# schematic.net
KiCad netlist of a schematic drawn in EasyEDA
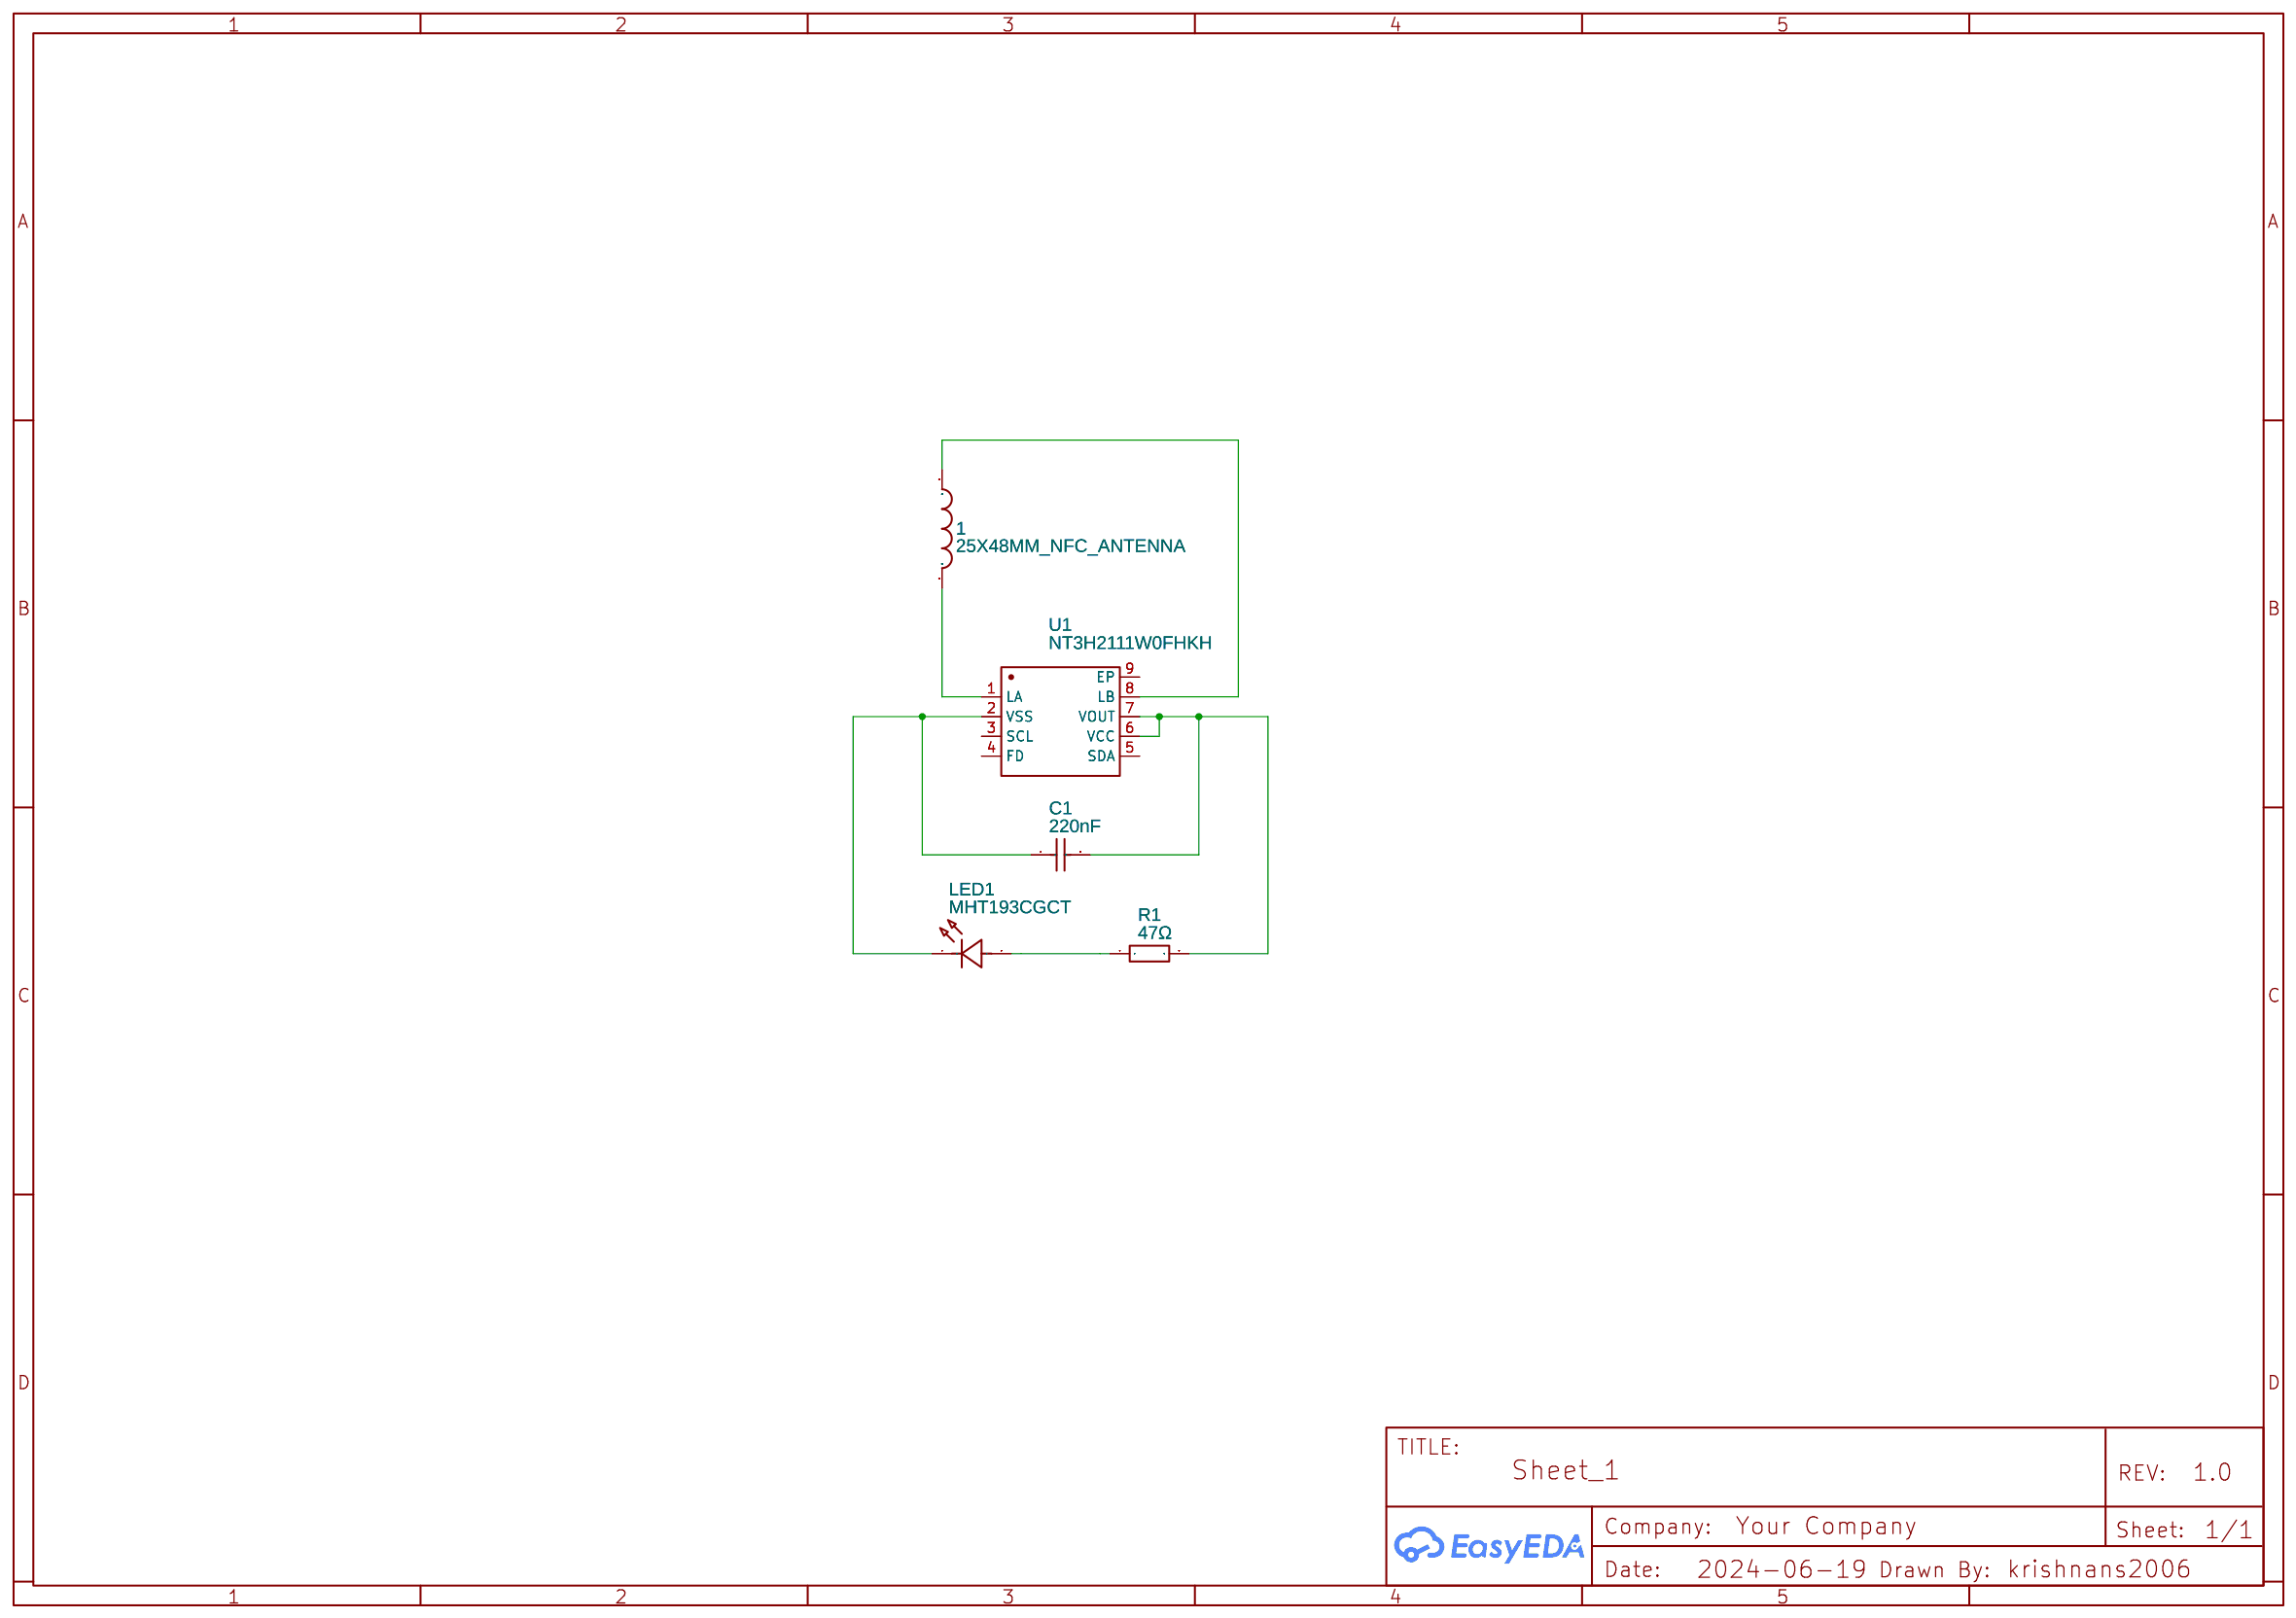
[diagram p0: schematic sheet]

(export (version "E")
  (design (tool "Eeschema 10.0.6"))
  (components
    (comp (ref "1") (value "25X48MM_NFC_ANTENNA") (libsource (lib "") (part "25X48MM_NFC_ANTENNA")))
    (comp (ref "C1")
      (value "220nF")
      (fields
        (field (name "Manufacturer Part") "CL10B224KA8NNNC")
        (field (name "Manufacturer") "SAMSUNG(三星)")
      )
      (libsource (lib "") (part "CL10B224KA8NNNC"))
    )
    (comp (ref "LED1")
      (value "MHT193CGCT")
      (fields (field (name "Manufacturer") "MEIHUA(美华)"))
      (libsource (lib "") (part "MHT193CGCT"))
    )
    (comp (ref "R1")
      (value "47Ω")
      (fields
        (field (name "Manufacturer Part") "0603WAF470JT5E")
        (field (name "Manufacturer") "UNI-ROYAL(厚声)")
      )
      (libsource (lib "") (part "0603WAF470JT5E"))
    )
    (comp (ref "U1")
      (value "NT3H2111W0FHKH")
      (fields (field (name "Manufacturer") "NXP(恩智浦)"))
      (libsource (lib "") (part "NT3H2111W0FHKH"))
    )
  )
  (nets
    (net (code "1") (name "Net-(LED1-A)") (class "Default")
      (node (ref "LED1") (pin "2") (pinfunction "A_2") (pintype "unspecified"))
      (node (ref "R1") (pin "1") (pinfunction "1_1") (pintype "input"))
    )
    (net (code "2") (name "Net-(LED1-K)") (class "Default")
      (node (ref "C1") (pin "1") (pinfunction "1_1") (pintype "input"))
      (node (ref "LED1") (pin "1") (pinfunction "K_1") (pintype "unspecified"))
      (node (ref "U1") (pin "2") (pinfunction "VSS_2") (pintype "unspecified"))
    )
    (net (code "3") (name "Net-(U1-LA)") (class "Default")
      (node (ref "1") (pin "P$2") (pinfunction "P$2_P$2") (pintype "bidirectional"))
      (node (ref "U1") (pin "1") (pinfunction "LA_1") (pintype "unspecified"))
    )
    (net (code "4") (name "Net-(U1-LB)") (class "Default")
      (node (ref "1") (pin "P$1") (pinfunction "P$1_P$1") (pintype "bidirectional"))
      (node (ref "U1") (pin "8") (pinfunction "LB_8") (pintype "unspecified"))
    )
    (net (code "5") (name "Net-(U1-VCC)") (class "Default")
      (node (ref "C1") (pin "2") (pinfunction "2_2") (pintype "input"))
      (node (ref "R1") (pin "2") (pinfunction "2_2") (pintype "input"))
      (node (ref "U1") (pin "6") (pinfunction "VCC_6") (pintype "unspecified"))
      (node (ref "U1") (pin "7") (pinfunction "VOUT_7") (pintype "unspecified"))
    )
    (net (code "6") (name "unconnected-(U1-EP-Pad9)") (class "Default")
      (node (ref "U1") (pin "9") (pinfunction "EP_9") (pintype "unspecified"))
    )
    (net (code "7") (name "unconnected-(U1-FD-Pad4)") (class "Default")
      (node (ref "U1") (pin "4") (pinfunction "FD_4") (pintype "unspecified"))
    )
    (net (code "8") (name "unconnected-(U1-SCL-Pad3)") (class "Default")
      (node (ref "U1") (pin "3") (pinfunction "SCL_3") (pintype "unspecified"))
    )
    (net (code "9") (name "unconnected-(U1-SDA-Pad5)") (class "Default")
      (node (ref "U1") (pin "5") (pinfunction "SDA_5") (pintype "unspecified"))
    )
  )
)
